# electron_v009.net
KiCad netlist of a schematic drawn in EAGLE
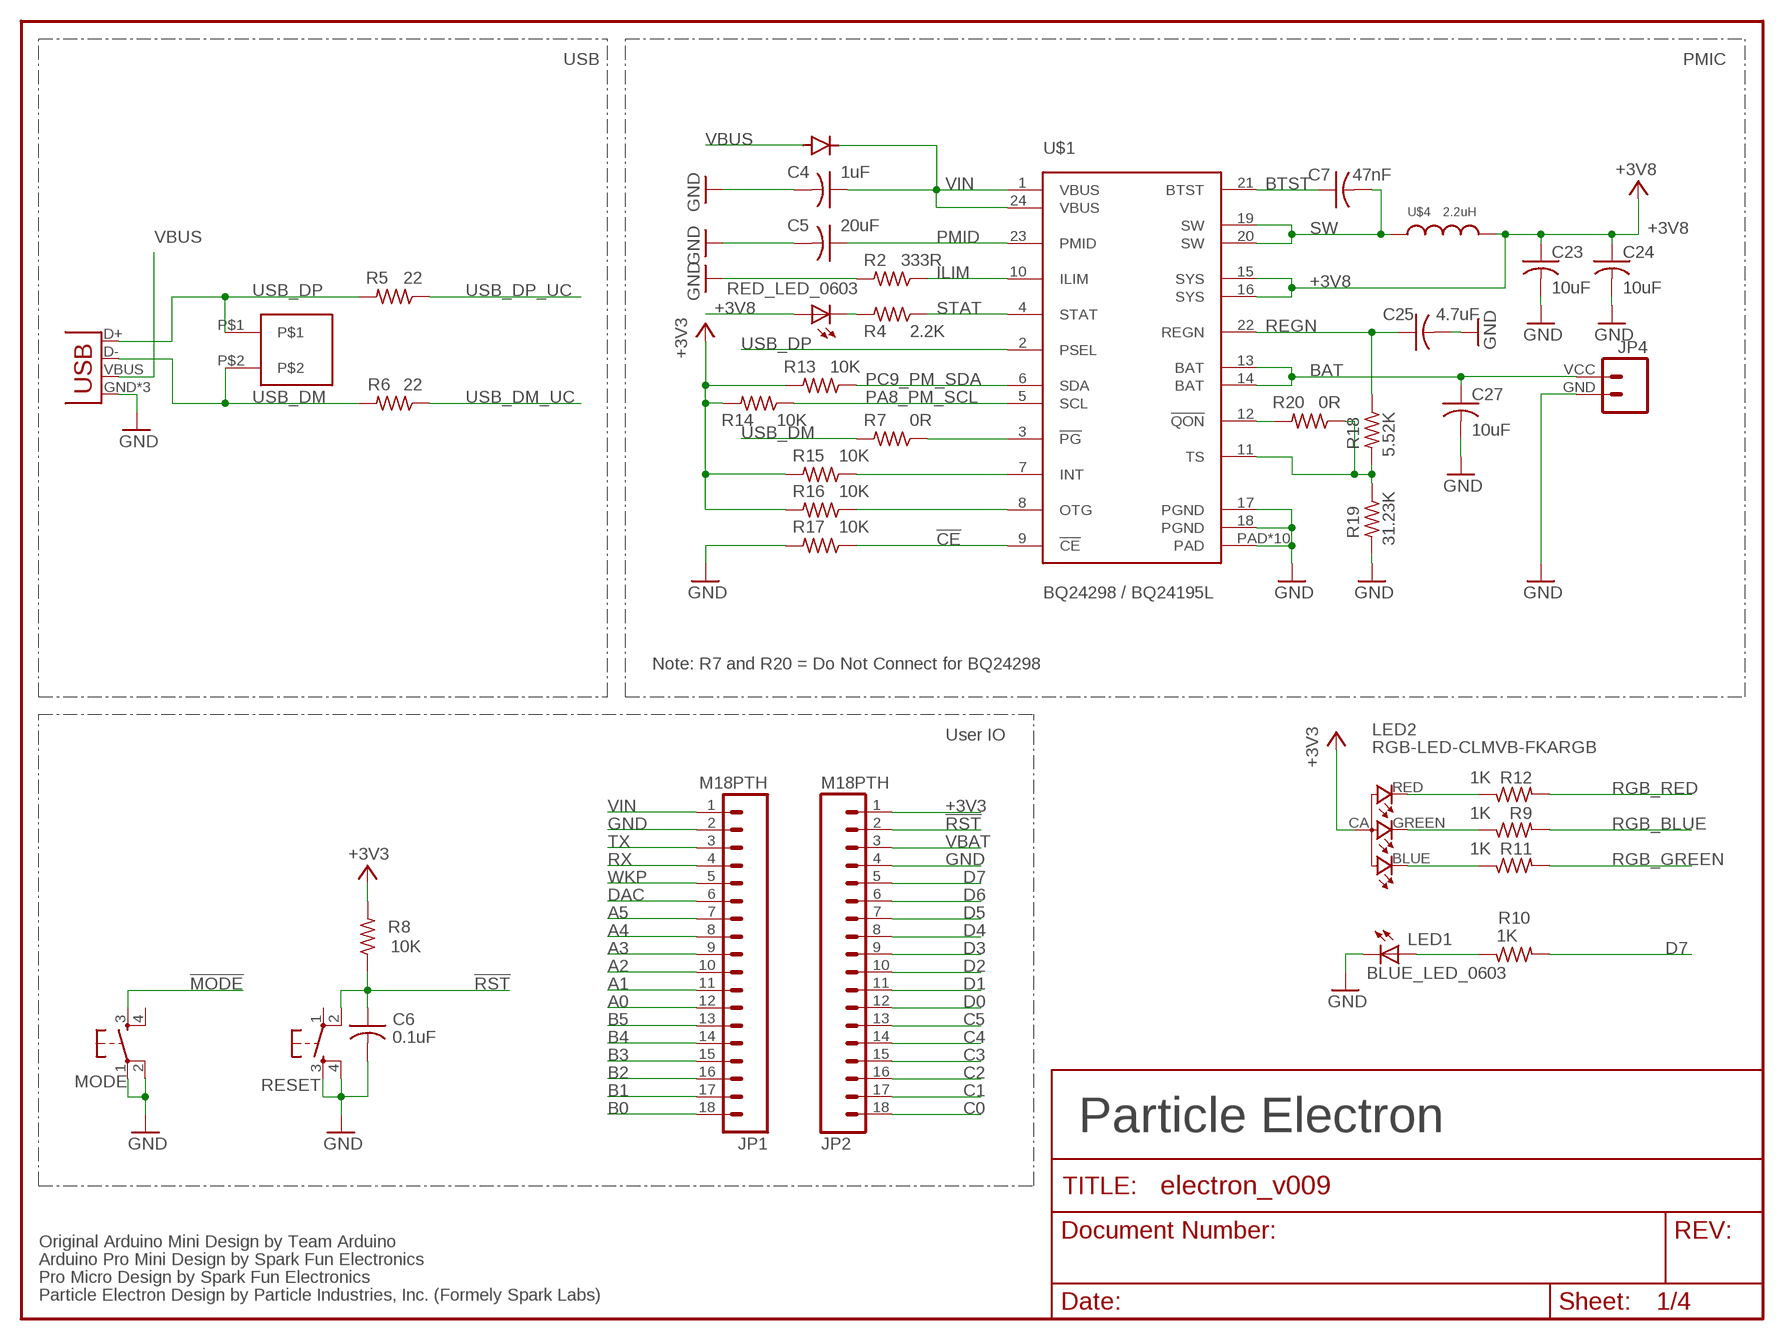
[diagram p0: schematic, sheet 1]
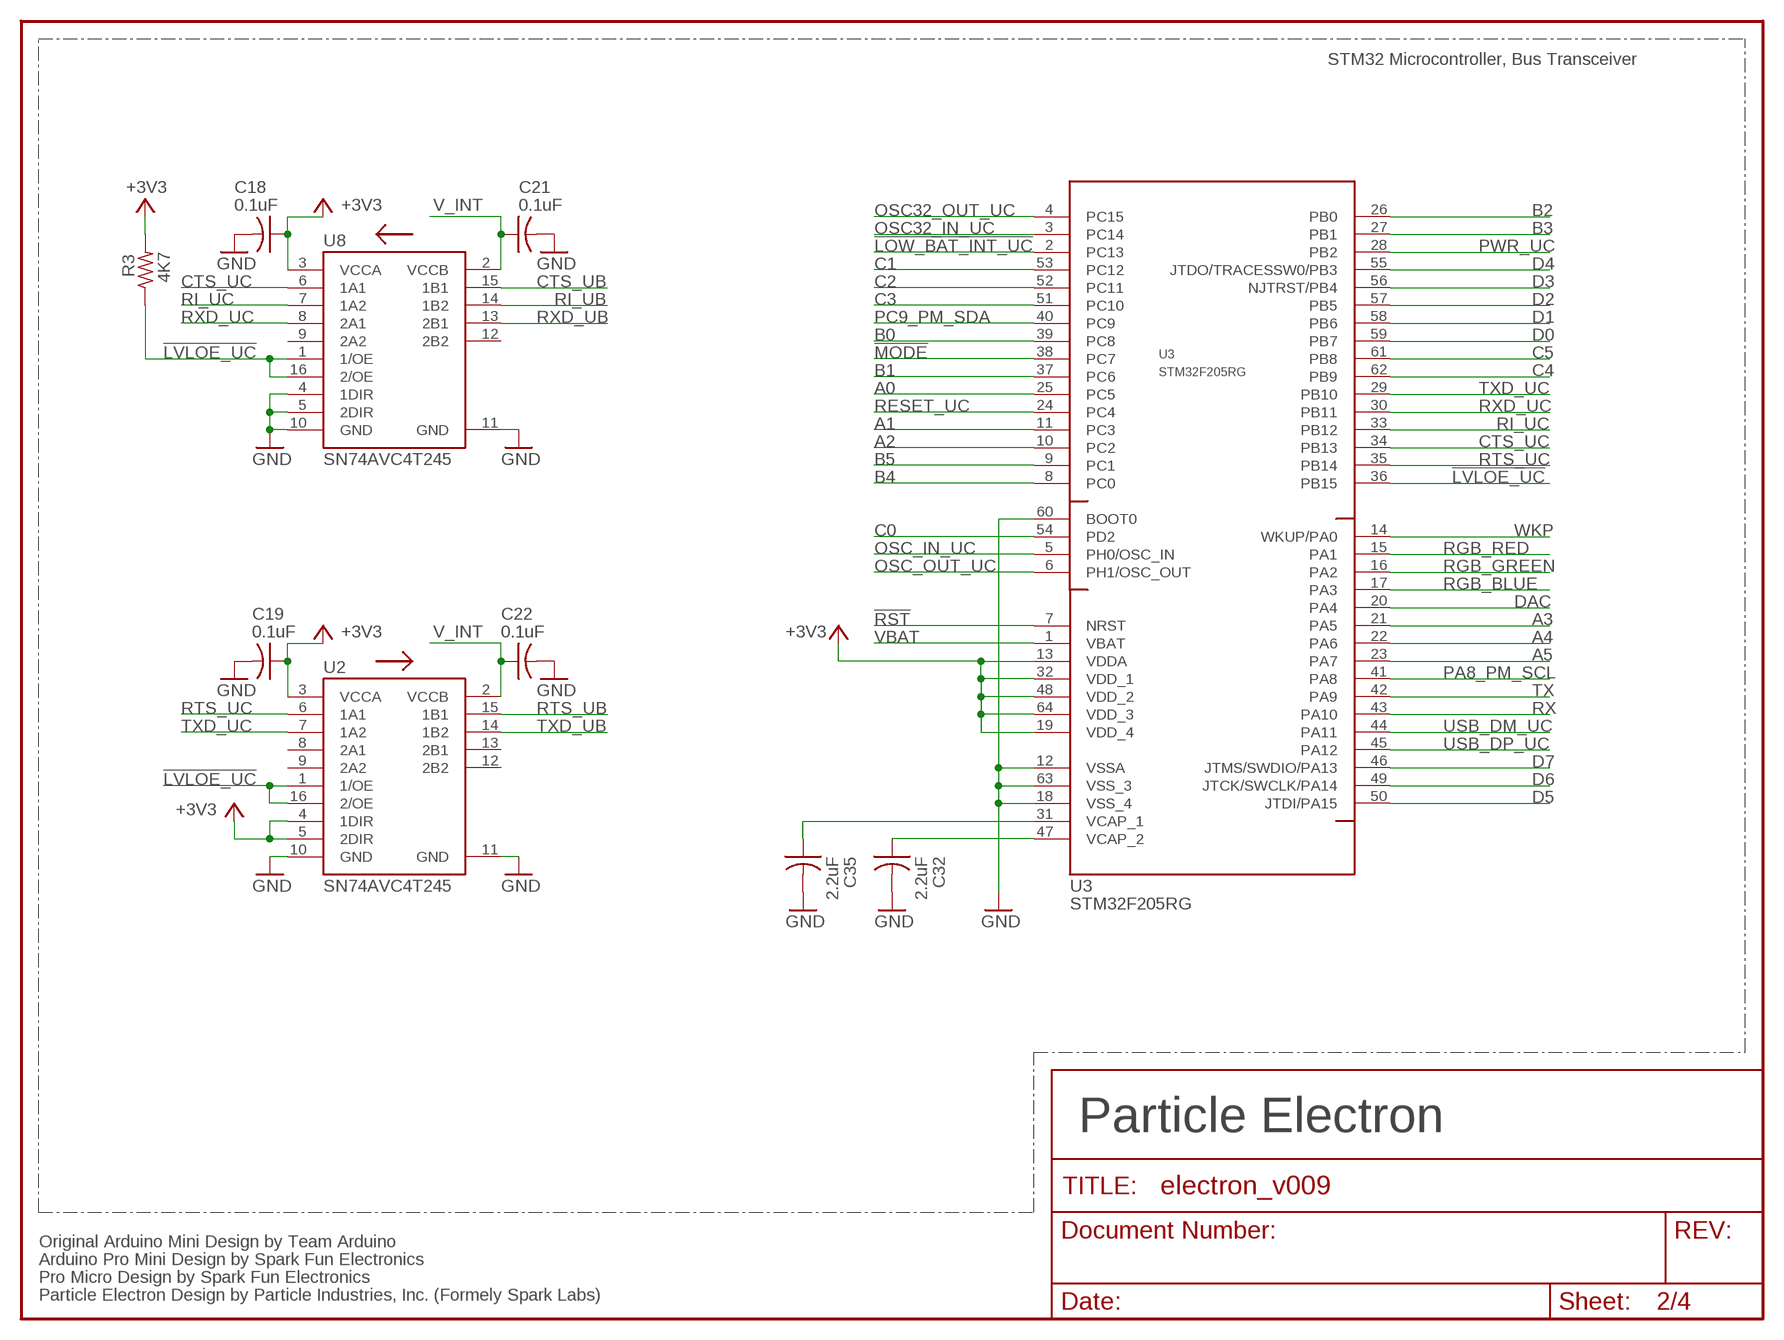
[diagram p1: schematic, sheet 2]
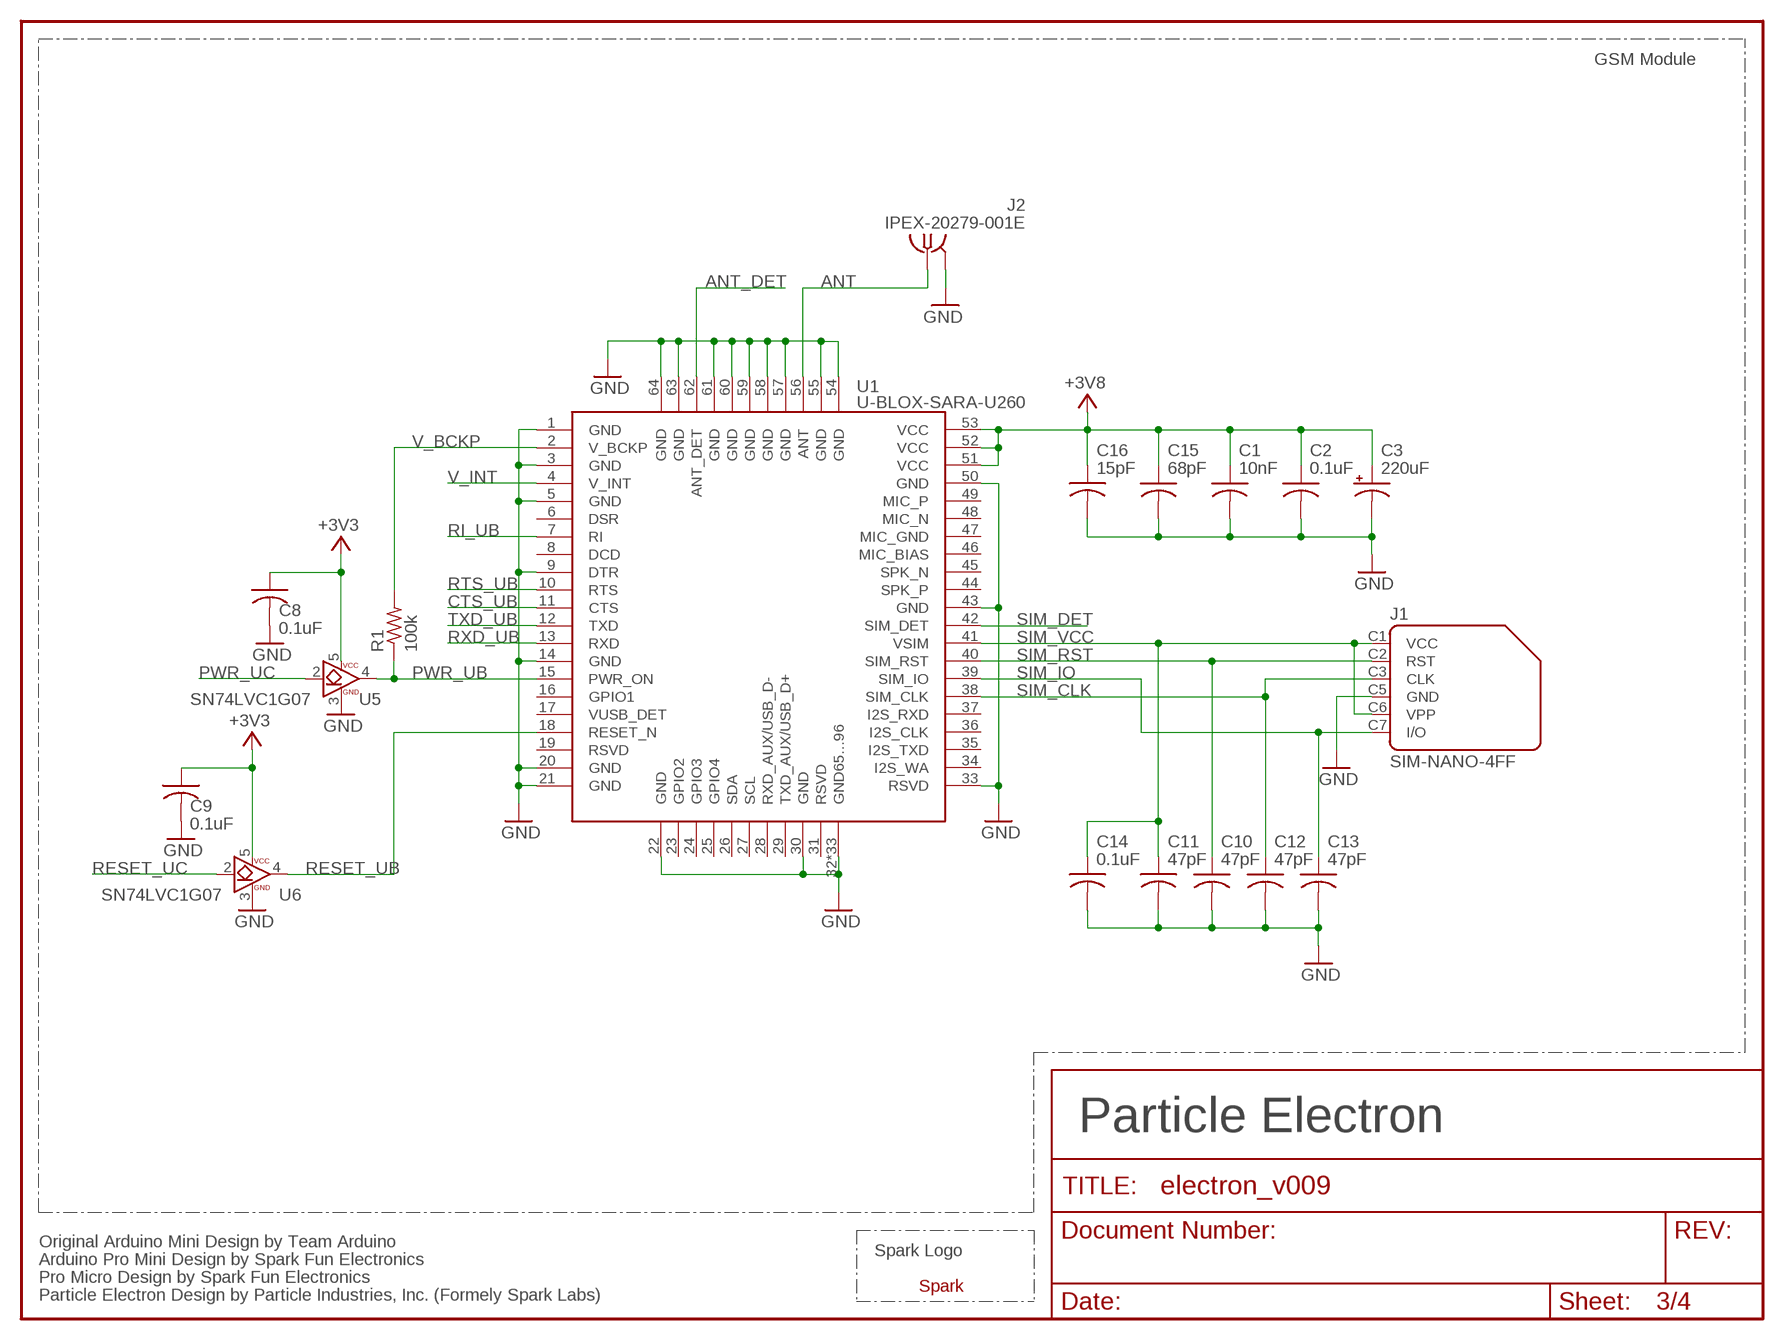
[diagram p2: schematic, sheet 3]
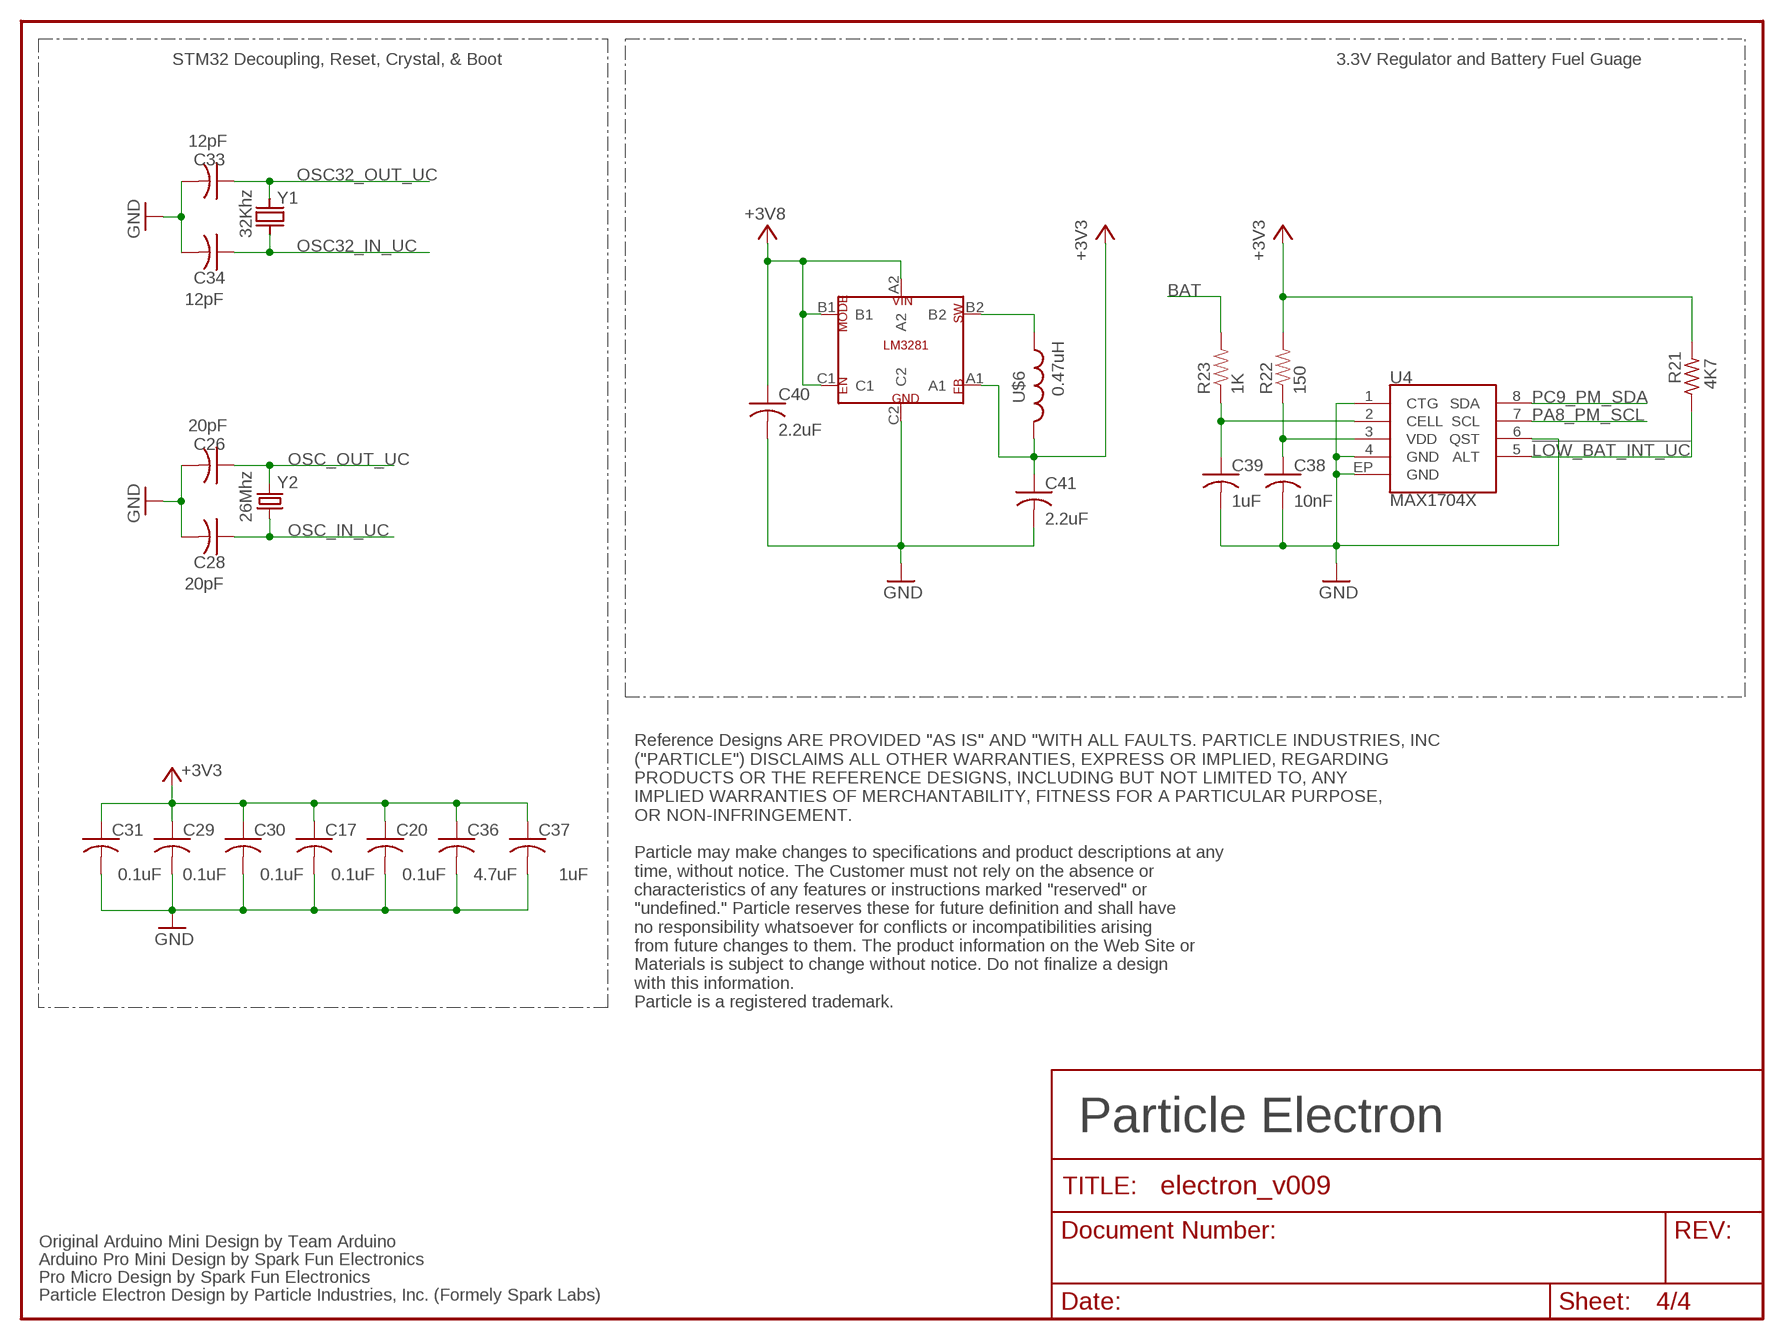
[diagram p3: schematic, sheet 4]

(export (version "E")
  (design (tool "Eeschema 10.0.6"))
  (components
    (comp (ref "C1")
      (value "10nF")
      (footprint "eagle-import:C0402_B")
      (libsource (lib "eagle-import") (part "C-US"))
    )
    (comp (ref "C2")
      (value "0.1uF")
      (footprint "eagle-import:C0402_B")
      (libsource (lib "eagle-import") (part "C-US"))
    )
    (comp (ref "C3")
      (value "220uF")
      (footprint "eagle-import:C_6032-28R")
      (libsource (lib "eagle-import") (part "CPOL-USC/6032-28R"))
    )
    (comp (ref "C8")
      (value "0.1uF")
      (footprint "eagle-import:C0402_B")
      (libsource (lib "eagle-import") (part "C-US"))
    )
    (comp (ref "C9")
      (value "0.1uF")
      (footprint "eagle-import:C0402_B")
      (libsource (lib "eagle-import") (part "C-US"))
    )
    (comp (ref "C10")
      (value "47pF")
      (footprint "eagle-import:C0402_B")
      (libsource (lib "eagle-import") (part "C-US"))
    )
    (comp (ref "C11")
      (value "47pF")
      (footprint "eagle-import:C0402_B")
      (libsource (lib "eagle-import") (part "C-US"))
    )
    (comp (ref "C12")
      (value "47pF")
      (footprint "eagle-import:C0402_B")
      (libsource (lib "eagle-import") (part "C-US"))
    )
    (comp (ref "C13")
      (value "47pF")
      (footprint "eagle-import:C0402_B")
      (libsource (lib "eagle-import") (part "C-US"))
    )
    (comp (ref "C14")
      (value "0.1uF")
      (footprint "eagle-import:C0402_B")
      (libsource (lib "eagle-import") (part "C-US"))
    )
    (comp (ref "C15")
      (value "68pF")
      (footprint "eagle-import:C0402_B")
      (libsource (lib "eagle-import") (part "C-US"))
    )
    (comp (ref "C16")
      (value "15pF")
      (footprint "eagle-import:C0402_B")
      (libsource (lib "eagle-import") (part "C-US"))
    )
    (comp (ref "J1")
      (value "SIM-NANO-4FF")
      (footprint "eagle-import:GCT-SIM8100")
      (libsource (lib "eagle-import") (part "SIM-NANO-4FF"))
    )
    (comp (ref "J2")
      (value "IPEX-20279-001E")
      (footprint "eagle-import:IPEX-20279-001E")
      (libsource (lib "eagle-import") (part "IPEX-20279-001E"))
    )
    (comp (ref "R1")
      (value "100k")
      (footprint "eagle-import:R0402_B")
      (libsource (lib "eagle-import") (part "R-US_"))
    )
    (comp (ref "U$2")
      (value "SPARK_LOGO2")
      (footprint "eagle-import:SPARK_LOGO2")
      (libsource (lib "eagle-import") (part "SPARK_LOGO2"))
    )
    (comp (ref "U1")
      (value "U-BLOX-SARA-U260")
      (footprint "eagle-import:U-BLOX-SARA-U2")
      (libsource (lib "eagle-import") (part "U-BLOX-SARA-U260"))
    )
    (comp (ref "U5")
      (value "SN74LVC1G07")
      (footprint "eagle-import:SC-70-5")
      (libsource (lib "eagle-import") (part "SN74LVC1G07"))
    )
    (comp (ref "U6")
      (value "SN74LVC1G07")
      (footprint "eagle-import:SC-70-5")
      (libsource (lib "eagle-import") (part "SN74LVC1G07"))
    )
    (comp (ref "C17")
      (value "0.1uF")
      (footprint "eagle-import:C0402_B")
      (libsource (lib "eagle-import") (part "C-US"))
    )
    (comp (ref "C20")
      (value "0.1uF")
      (footprint "eagle-import:C0402_B")
      (libsource (lib "eagle-import") (part "C-US"))
    )
    (comp (ref "C26")
      (value "20pF")
      (footprint "eagle-import:C0402_B")
      (libsource (lib "eagle-import") (part "C-US"))
    )
    (comp (ref "C28")
      (value "20pF")
      (footprint "eagle-import:C0402_B")
      (libsource (lib "eagle-import") (part "C-US"))
    )
    (comp (ref "C29")
      (value "0.1uF")
      (footprint "eagle-import:C0402_B")
      (libsource (lib "eagle-import") (part "C-US"))
    )
    (comp (ref "C30")
      (value "0.1uF")
      (footprint "eagle-import:C0402_B")
      (libsource (lib "eagle-import") (part "C-US"))
    )
    (comp (ref "C31")
      (value "0.1uF")
      (footprint "eagle-import:C0402_B")
      (libsource (lib "eagle-import") (part "C-US"))
    )
    (comp (ref "C33")
      (value "12pF")
      (footprint "eagle-import:C0402_B")
      (libsource (lib "eagle-import") (part "C-US"))
    )
    (comp (ref "C34")
      (value "12pF")
      (footprint "eagle-import:C0402_B")
      (libsource (lib "eagle-import") (part "C-US"))
    )
    (comp (ref "C36")
      (value "4.7uF")
      (footprint "eagle-import:C0402_B")
      (libsource (lib "eagle-import") (part "C-US"))
    )
    (comp (ref "C37")
      (value "1uF")
      (footprint "eagle-import:C0402_B")
      (libsource (lib "eagle-import") (part "C-US"))
    )
    (comp (ref "C38")
      (value "10nF")
      (footprint "eagle-import:C0402_B")
      (libsource (lib "eagle-import") (part "C-US"))
    )
    (comp (ref "C39")
      (value "1uF")
      (footprint "eagle-import:C0402_B")
      (libsource (lib "eagle-import") (part "C-US"))
    )
    (comp (ref "C40")
      (value "2.2uF")
      (footprint "eagle-import:C0603_B")
      (libsource (lib "eagle-import") (part "C-US0603"))
    )
    (comp (ref "C41")
      (value "2.2uF")
      (footprint "eagle-import:C0603_B")
      (libsource (lib "eagle-import") (part "C-US0603"))
    )
    (comp (ref "R21")
      (value "4K7")
      (footprint "eagle-import:R0402_B")
      (libsource (lib "eagle-import") (part "R-US_"))
    )
    (comp (ref "R22")
      (value "150")
      (footprint "eagle-import:0603-RES")
      (libsource (lib "eagle-import") (part "RESISTOR0603-RES"))
    )
    (comp (ref "R23")
      (value "1K")
      (footprint "eagle-import:0603-RES")
      (libsource (lib "eagle-import") (part "RESISTOR0603-RES"))
    )
    (comp (ref "U$5")
      (value "LM3281_DSBGA")
      (footprint "eagle-import:DSBGA")
      (libsource (lib "eagle-import") (part "LM3281_DSBGA"))
    )
    (comp (ref "U$6")
      (value "0.47uH")
      (footprint "eagle-import:0805")
      (libsource (lib "eagle-import") (part "INDUCTOR0805"))
    )
    (comp (ref "U4")
      (value "MAX1704X")
      (footprint "eagle-import:TDFN-8")
      (libsource (lib "eagle-import") (part "MAX1704X"))
    )
    (comp (ref "Y1")
      (value "32Khz")
      (footprint "eagle-import:FC135")
      (libsource (lib "eagle-import") (part "Q_FC135"))
    )
    (comp (ref "Y2")
      (value "26Mhz")
      (footprint "eagle-import:CRYSTAL-SMD-5X3")
      (libsource (lib "eagle-import") (part "CRYSTAL5X3"))
    )
    (comp (ref "C18")
      (value "0.1uF")
      (footprint "eagle-import:C0402_B")
      (libsource (lib "eagle-import") (part "C-US"))
    )
    (comp (ref "C19")
      (value "0.1uF")
      (footprint "eagle-import:C0402_B")
      (libsource (lib "eagle-import") (part "C-US"))
    )
    (comp (ref "C21")
      (value "0.1uF")
      (footprint "eagle-import:C0402_B")
      (libsource (lib "eagle-import") (part "C-US"))
    )
    (comp (ref "C22")
      (value "0.1uF")
      (footprint "eagle-import:C0402_B")
      (libsource (lib "eagle-import") (part "C-US"))
    )
    (comp (ref "C32")
      (value "2.2uF")
      (footprint "eagle-import:C0402_B")
      (libsource (lib "eagle-import") (part "C-US"))
    )
    (comp (ref "C35")
      (value "2.2uF")
      (footprint "eagle-import:C0402_B")
      (libsource (lib "eagle-import") (part "C-US"))
    )
    (comp (ref "R3")
      (value "4K7")
      (footprint "eagle-import:R0402_B")
      (libsource (lib "eagle-import") (part "R-US_"))
    )
    (comp (ref "U2")
      (value "SN74AVC4T245")
      (footprint "eagle-import:UFQFN-16")
      (libsource (lib "eagle-import") (part "SN74AVC4T245"))
    )
    (comp (ref "U3")
      (value "STM32F205RG")
      (footprint "eagle-import:LQFP64")
      (libsource (lib "eagle-import") (part "STM32F20XR"))
    )
    (comp (ref "U8")
      (value "SN74AVC4T245")
      (footprint "eagle-import:UFQFN-16")
      (libsource (lib "eagle-import") (part "SN74AVC4T245"))
    )
    (comp (ref "BLUE_LED_0603")
      (value "LED0603")
      (footprint "eagle-import:LED-0603")
      (libsource (lib "eagle-import") (part "LED0603"))
    )
    (comp (ref "C4")
      (value "1uF")
      (footprint "eagle-import:C0603_B")
      (libsource (lib "eagle-import") (part "C-US0603"))
    )
    (comp (ref "C5")
      (value "20uF")
      (footprint "eagle-import:C0603_B")
      (libsource (lib "eagle-import") (part "C-US0603"))
    )
    (comp (ref "C6")
      (value "0.1uF")
      (footprint "eagle-import:C0402_B")
      (libsource (lib "eagle-import") (part "C-US"))
    )
    (comp (ref "C7")
      (value "47nF")
      (footprint "eagle-import:C0402_B")
      (libsource (lib "eagle-import") (part "C-US"))
    )
    (comp (ref "C23")
      (value "10uF")
      (footprint "eagle-import:C0603_B")
      (libsource (lib "eagle-import") (part "C-US0603"))
    )
    (comp (ref "C24")
      (value "10uF")
      (footprint "eagle-import:C0603_B")
      (libsource (lib "eagle-import") (part "C-US0603"))
    )
    (comp (ref "C25")
      (value "4.7uF")
      (footprint "eagle-import:C0603_B")
      (libsource (lib "eagle-import") (part "C-US0603"))
    )
    (comp (ref "C27")
      (value "10uF")
      (footprint "eagle-import:C0603_B")
      (libsource (lib "eagle-import") (part "C-US0603"))
    )
    (comp (ref "JP1")
      (value "M18PTH")
      (footprint "eagle-import:1X18-SMALL-PADS")
      (libsource (lib "eagle-import") (part "M18PTH"))
    )
    (comp (ref "JP2")
      (value "M18PTH")
      (footprint "eagle-import:1X18-SMALL-PADS")
      (libsource (lib "eagle-import") (part "M18PTH"))
    )
    (comp (ref "JP4")
      (value "M024UCON-15767")
      (footprint "eagle-import:JST-2-SMD-VERT")
      (libsource (lib "eagle-import") (part "M024UCON-15767"))
    )
    (comp (ref "LED2")
      (value "RGB-LED-CLMVB-FKARGB")
      (footprint "eagle-import:PLCC4-2MM-RGB")
      (libsource (lib "eagle-import") (part "RGB-LED-CLMVB-FKARGB"))
    )
    (comp (ref "MODE")
      (value "KMR211GLFS")
      (footprint "eagle-import:TACTILE_SWITCH_SMD")
      (libsource (lib "eagle-import") (part "TAC_SWITCHSMD"))
    )
    (comp (ref "R2")
      (value "333R")
      (footprint "eagle-import:R0402_B")
      (libsource (lib "eagle-import") (part "R-US_"))
    )
    (comp (ref "R4")
      (value "2.2K")
      (footprint "eagle-import:R0402_B")
      (libsource (lib "eagle-import") (part "R-US_"))
    )
    (comp (ref "R5")
      (value "22")
      (footprint "eagle-import:R0402_B")
      (libsource (lib "eagle-import") (part "R-US_"))
    )
    (comp (ref "R6")
      (value "22")
      (footprint "eagle-import:R0402_B")
      (libsource (lib "eagle-import") (part "R-US_"))
    )
    (comp (ref "R7")
      (value "0R")
      (footprint "eagle-import:R0402_B")
      (libsource (lib "eagle-import") (part "R-US_"))
    )
    (comp (ref "R8")
      (value "10K")
      (footprint "eagle-import:R0402_B")
      (libsource (lib "eagle-import") (part "R-US_"))
    )
    (comp (ref "R9")
      (value "1K")
      (footprint "eagle-import:R0402_B")
      (libsource (lib "eagle-import") (part "R-US_"))
    )
    (comp (ref "R10")
      (value "1K")
      (footprint "eagle-import:R0402_B")
      (libsource (lib "eagle-import") (part "R-US_"))
    )
    (comp (ref "R11")
      (value "1K")
      (footprint "eagle-import:R0402_B")
      (libsource (lib "eagle-import") (part "R-US_"))
    )
    (comp (ref "R12")
      (value "1K")
      (footprint "eagle-import:R0402_B")
      (libsource (lib "eagle-import") (part "R-US_"))
    )
    (comp (ref "R13")
      (value "10K")
      (footprint "eagle-import:R0402_B")
      (libsource (lib "eagle-import") (part "R-US_"))
    )
    (comp (ref "R14")
      (value "10K")
      (footprint "eagle-import:R0402_B")
      (libsource (lib "eagle-import") (part "R-US_"))
    )
    (comp (ref "R15")
      (value "10K")
      (footprint "eagle-import:R0402_B")
      (libsource (lib "eagle-import") (part "R-US_"))
    )
    (comp (ref "R16")
      (value "10K")
      (footprint "eagle-import:R0402_B")
      (libsource (lib "eagle-import") (part "R-US_"))
    )
    (comp (ref "R17")
      (value "10K")
      (footprint "eagle-import:R0402_B")
      (libsource (lib "eagle-import") (part "R-US_"))
    )
    (comp (ref "R18")
      (value "5.52K")
      (footprint "eagle-import:R0402_B")
      (libsource (lib "eagle-import") (part "R-US_"))
    )
    (comp (ref "R19")
      (value "31.23K")
      (footprint "eagle-import:R0402_B")
      (libsource (lib "eagle-import") (part "R-US_"))
    )
    (comp (ref "R20")
      (value "0R")
      (footprint "eagle-import:R0402_B")
      (libsource (lib "eagle-import") (part "R-US_"))
    )
    (comp (ref "RED_LED_0603")
      (value "LED0603")
      (footprint "eagle-import:LED-0603")
      (libsource (lib "eagle-import") (part "LED0603"))
    )
    (comp (ref "RESET")
      (value "KMR211GLFS")
      (footprint "eagle-import:TACTILE_SWITCH_SMD")
      (libsource (lib "eagle-import") (part "TAC_SWITCHSMD"))
    )
    (comp (ref "U$1")
      (value "BQ24298 / BQ24195L")
      (footprint "eagle-import:QFN24")
      (libsource (lib "eagle-import") (part "BQ24298RTWR"))
    )
    (comp (ref "U$3")
      (value "DIODE")
      (footprint "eagle-import:DIODE-DO-220AA(SMP)")
      (libsource (lib "eagle-import") (part "DIODE"))
    )
    (comp (ref "U$4")
      (value "2.2uH")
      (footprint "eagle-import:4020TYPE")
      (libsource (lib "eagle-import") (part "INDUCTOR4020"))
    )
    (comp (ref "U$7")
      (value "M02_0.05_HEADER")
      (footprint "eagle-import:M02_0.05_HEADER")
      (libsource (lib "eagle-import") (part "M02_0.05_HEADER"))
    )
    (comp (ref "X1")
      (value "USB-MICROB")
      (footprint "eagle-import:USB-MICROB-SLOT-HOLE")
      (libsource (lib "eagle-import") (part "USBUSB-MICROB-SLOT-HOLE"))
    )
  )
  (nets
    (net (code "1") (name "+3V3") (class "Default")
      (node (ref "C17") (pin "1") (pinfunction "1_1") (pintype "passive"))
      (node (ref "C18") (pin "1") (pinfunction "1_1") (pintype "passive"))
      (node (ref "C19") (pin "1") (pinfunction "1_1") (pintype "passive"))
      (node (ref "C20") (pin "1") (pinfunction "1_1") (pintype "passive"))
      (node (ref "C29") (pin "1") (pinfunction "1_1") (pintype "passive"))
      (node (ref "C30") (pin "1") (pinfunction "1_1") (pintype "passive"))
      (node (ref "C31") (pin "1") (pinfunction "1_1") (pintype "passive"))
      (node (ref "C36") (pin "1") (pinfunction "1_1") (pintype "passive"))
      (node (ref "C37") (pin "1") (pinfunction "1_1") (pintype "passive"))
      (node (ref "C41") (pin "1") (pinfunction "1_1") (pintype "passive"))
      (node (ref "C8") (pin "1") (pinfunction "1_1") (pintype "passive"))
      (node (ref "C9") (pin "1") (pinfunction "1_1") (pintype "passive"))
      (node (ref "JP2") (pin "1") (pinfunction "1_1") (pintype "passive"))
      (node (ref "LED2") (pin "CA") (pinfunction "1_CA") (pintype "passive"))
      (node (ref "R13") (pin "2") (pinfunction "2_2") (pintype "passive"))
      (node (ref "R14") (pin "2") (pinfunction "2_2") (pintype "passive"))
      (node (ref "R15") (pin "2") (pinfunction "2_2") (pintype "passive"))
      (node (ref "R16") (pin "2") (pinfunction "2_2") (pintype "passive"))
      (node (ref "R21") (pin "2") (pinfunction "2_2") (pintype "passive"))
      (node (ref "R22") (pin "2") (pinfunction "2_2") (pintype "passive"))
      (node (ref "R3") (pin "2") (pinfunction "2_2") (pintype "passive"))
      (node (ref "R8") (pin "2") (pinfunction "2_2") (pintype "passive"))
      (node (ref "U$5") (pin "A1") (pinfunction "A1_A1") (pintype "bidirectional"))
      (node (ref "U$6") (pin "2") (pinfunction "2_2") (pintype "passive"))
      (node (ref "U2") (pin "3") (pinfunction "VCCA_3") (pintype "bidirectional"))
      (node (ref "U2") (pin "4") (pinfunction "1DIR_4") (pintype "bidirectional"))
      (node (ref "U2") (pin "5") (pinfunction "2DIR_5") (pintype "bidirectional"))
      (node (ref "U3") (pin "13") (pinfunction "VDDA_13") (pintype "power_in"))
      (node (ref "U3") (pin "19") (pinfunction "VDD_4_19") (pintype "power_in"))
      (node (ref "U3") (pin "32") (pinfunction "VDD_1_32") (pintype "power_in"))
      (node (ref "U3") (pin "48") (pinfunction "VDD_2_48") (pintype "power_in"))
      (node (ref "U3") (pin "64") (pinfunction "VDD_3_64") (pintype "power_in"))
      (node (ref "U5") (pin "5") (pinfunction "VCC_5") (pintype "bidirectional"))
      (node (ref "U6") (pin "5") (pinfunction "VCC_5") (pintype "bidirectional"))
      (node (ref "U8") (pin "3") (pinfunction "VCCA_3") (pintype "bidirectional"))
    )
    (net (code "2") (name "+3V8") (class "Default")
      (node (ref "C1") (pin "1") (pinfunction "1_1") (pintype "passive"))
      (node (ref "C15") (pin "1") (pinfunction "1_1") (pintype "passive"))
      (node (ref "C16") (pin "1") (pinfunction "1_1") (pintype "passive"))
      (node (ref "C2") (pin "1") (pinfunction "1_1") (pintype "passive"))
      (node (ref "C23") (pin "1") (pinfunction "1_1") (pintype "passive"))
      (node (ref "C24") (pin "1") (pinfunction "1_1") (pintype "passive"))
      (node (ref "C3") (pin "+") (pinfunction "+_+") (pintype "passive"))
      (node (ref "C40") (pin "1") (pinfunction "1_1") (pintype "passive"))
      (node (ref "RED_LED_0603") (pin "A") (pinfunction "A_A") (pintype "passive"))
      (node (ref "U$1") (pin "15") (pinfunction "SYS_15") (pintype "power_in"))
      (node (ref "U$1") (pin "16") (pinfunction "SYS_16") (pintype "power_in"))
      (node (ref "U$4") (pin "P$2") (pinfunction "2_P$2") (pintype "bidirectional"))
      (node (ref "U$5") (pin "A2") (pinfunction "A2_A2") (pintype "bidirectional"))
      (node (ref "U$5") (pin "B1") (pinfunction "B1_B1") (pintype "bidirectional"))
      (node (ref "U$5") (pin "C1") (pinfunction "C1_C1") (pintype "bidirectional"))
      (node (ref "U1") (pin "51") (pinfunction "VCC_51") (pintype "bidirectional"))
      (node (ref "U1") (pin "52") (pinfunction "VCC_52") (pintype "bidirectional"))
      (node (ref "U1") (pin "53") (pinfunction "VCC_53") (pintype "bidirectional"))
    )
    (net (code "3") (name "A0") (class "Default")
      (node (ref "JP1") (pin "12") (pinfunction "12_12") (pintype "passive"))
      (node (ref "U3") (pin "25") (pinfunction "PC5_25") (pintype "bidirectional"))
    )
    (net (code "4") (name "A1") (class "Default")
      (node (ref "JP1") (pin "11") (pinfunction "11_11") (pintype "passive"))
      (node (ref "U3") (pin "11") (pinfunction "PC3_11") (pintype "bidirectional"))
    )
    (net (code "5") (name "A2") (class "Default")
      (node (ref "JP1") (pin "10") (pinfunction "10_10") (pintype "passive"))
      (node (ref "U3") (pin "10") (pinfunction "PC2_10") (pintype "bidirectional"))
    )
    (net (code "6") (name "A3") (class "Default")
      (node (ref "JP1") (pin "9") (pinfunction "9_9") (pintype "passive"))
      (node (ref "U3") (pin "21") (pinfunction "PA5_21") (pintype "bidirectional"))
    )
    (net (code "7") (name "A4") (class "Default")
      (node (ref "JP1") (pin "8") (pinfunction "8_8") (pintype "passive"))
      (node (ref "U3") (pin "22") (pinfunction "PA6_22") (pintype "bidirectional"))
    )
    (net (code "8") (name "A5") (class "Default")
      (node (ref "JP1") (pin "7") (pinfunction "7_7") (pintype "passive"))
      (node (ref "U3") (pin "23") (pinfunction "PA7_23") (pintype "bidirectional"))
    )
    (net (code "9") (name "ANT") (class "Default")
      (node (ref "J2") (pin "1") (pinfunction "1_1") (pintype "passive"))
      (node (ref "U1") (pin "56") (pinfunction "ANT_56") (pintype "bidirectional"))
    )
    (net (code "10") (name "ANT_DET") (class "Default")
      (node (ref "U1") (pin "62") (pinfunction "ANT_DET_62") (pintype "bidirectional"))
    )
    (net (code "11") (name "B0") (class "Default")
      (node (ref "JP1") (pin "18") (pinfunction "18_18") (pintype "passive"))
      (node (ref "U3") (pin "39") (pinfunction "PC8_39") (pintype "bidirectional"))
    )
    (net (code "12") (name "B1") (class "Default")
      (node (ref "JP1") (pin "17") (pinfunction "17_17") (pintype "passive"))
      (node (ref "U3") (pin "37") (pinfunction "PC6_37") (pintype "bidirectional"))
    )
    (net (code "13") (name "B2") (class "Default")
      (node (ref "JP1") (pin "16") (pinfunction "16_16") (pintype "passive"))
      (node (ref "U3") (pin "26") (pinfunction "PB0_26") (pintype "bidirectional"))
    )
    (net (code "14") (name "B3") (class "Default")
      (node (ref "JP1") (pin "15") (pinfunction "15_15") (pintype "passive"))
      (node (ref "U3") (pin "27") (pinfunction "PB1_27") (pintype "bidirectional"))
    )
    (net (code "15") (name "B4") (class "Default")
      (node (ref "JP1") (pin "14") (pinfunction "14_14") (pintype "passive"))
      (node (ref "U3") (pin "8") (pinfunction "PC0_8") (pintype "bidirectional"))
    )
    (net (code "16") (name "B5") (class "Default")
      (node (ref "JP1") (pin "13") (pinfunction "13_13") (pintype "passive"))
      (node (ref "U3") (pin "9") (pinfunction "PC1_9") (pintype "bidirectional"))
    )
    (net (code "17") (name "BAT") (class "Default")
      (node (ref "C27") (pin "1") (pinfunction "1_1") (pintype "passive"))
      (node (ref "JP4") (pin "VCC") (pinfunction "2_VCC") (pintype "passive"))
      (node (ref "R23") (pin "2") (pinfunction "2_2") (pintype "passive"))
      (node (ref "U$1") (pin "13") (pinfunction "BAT_13") (pintype "passive"))
      (node (ref "U$1") (pin "14") (pinfunction "BAT_14") (pintype "power_in"))
    )
    (net (code "18") (name "BTST") (class "Default")
      (node (ref "C7") (pin "1") (pinfunction "1_1") (pintype "passive"))
      (node (ref "U$1") (pin "21") (pinfunction "BTST_21") (pintype "bidirectional"))
    )
    (net (code "19") (name "C0") (class "Default")
      (node (ref "JP2") (pin "18") (pinfunction "18_18") (pintype "passive"))
      (node (ref "U3") (pin "54") (pinfunction "PD2_54") (pintype "bidirectional"))
    )
    (net (code "20") (name "C1") (class "Default")
      (node (ref "JP2") (pin "17") (pinfunction "17_17") (pintype "passive"))
      (node (ref "U3") (pin "53") (pinfunction "PC12_53") (pintype "bidirectional"))
    )
    (net (code "21") (name "C2") (class "Default")
      (node (ref "JP2") (pin "16") (pinfunction "16_16") (pintype "passive"))
      (node (ref "U3") (pin "52") (pinfunction "PC11_52") (pintype "bidirectional"))
    )
    (net (code "22") (name "C3") (class "Default")
      (node (ref "JP2") (pin "15") (pinfunction "15_15") (pintype "passive"))
      (node (ref "U3") (pin "51") (pinfunction "PC10_51") (pintype "bidirectional"))
    )
    (net (code "23") (name "C4") (class "Default")
      (node (ref "JP2") (pin "14") (pinfunction "14_14") (pintype "passive"))
      (node (ref "U3") (pin "62") (pinfunction "PB9_62") (pintype "bidirectional"))
    )
    (net (code "24") (name "C5") (class "Default")
      (node (ref "JP2") (pin "13") (pinfunction "13_13") (pintype "passive"))
      (node (ref "U3") (pin "61") (pinfunction "PB8_61") (pintype "bidirectional"))
    )
    (net (code "25") (name "CTS_UB") (class "Default")
      (node (ref "U1") (pin "11") (pinfunction "CTS_11") (pintype "bidirectional"))
      (node (ref "U8") (pin "15") (pinfunction "1B1_15") (pintype "bidirectional"))
    )
    (net (code "26") (name "CTS_UC") (class "Default")
      (node (ref "U3") (pin "34") (pinfunction "PB13_34") (pintype "bidirectional"))
      (node (ref "U8") (pin "6") (pinfunction "1A1_6") (pintype "bidirectional"))
    )
    (net (code "27") (name "D0") (class "Default")
      (node (ref "JP2") (pin "12") (pinfunction "12_12") (pintype "passive"))
      (node (ref "U3") (pin "59") (pinfunction "PB7_59") (pintype "bidirectional"))
    )
    (net (code "28") (name "D1") (class "Default")
      (node (ref "JP2") (pin "11") (pinfunction "11_11") (pintype "passive"))
      (node (ref "U3") (pin "58") (pinfunction "PB6_58") (pintype "bidirectional"))
    )
    (net (code "29") (name "D2") (class "Default")
      (node (ref "JP2") (pin "10") (pinfunction "10_10") (pintype "passive"))
      (node (ref "U3") (pin "57") (pinfunction "PB5_57") (pintype "bidirectional"))
    )
    (net (code "30") (name "D3") (class "Default")
      (node (ref "JP2") (pin "9") (pinfunction "9_9") (pintype "passive"))
      (node (ref "U3") (pin "56") (pinfunction "NJTRST/PB4_56") (pintype "bidirectional"))
    )
    (net (code "31") (name "D4") (class "Default")
      (node (ref "JP2") (pin "8") (pinfunction "8_8") (pintype "passive"))
      (node (ref "U3") (pin "55") (pinfunction "JTDO/TRACESSW0/PB3_55") (pintype "bidirectional"))
    )
    (net (code "32") (name "D5") (class "Default")
      (node (ref "JP2") (pin "7") (pinfunction "7_7") (pintype "passive"))
      (node (ref "U3") (pin "50") (pinfunction "JTDI/PA15_50") (pintype "bidirectional"))
    )
    (net (code "33") (name "D6") (class "Default")
      (node (ref "JP2") (pin "6") (pinfunction "6_6") (pintype "passive"))
      (node (ref "U3") (pin "49") (pinfunction "JTCK/SWCLK/PA14_49") (pintype "bidirectional"))
    )
    (net (code "34") (name "D7") (class "Default")
      (node (ref "JP2") (pin "5") (pinfunction "5_5") (pintype "passive"))
      (node (ref "R10") (pin "2") (pinfunction "2_2") (pintype "passive"))
      (node (ref "U3") (pin "46") (pinfunction "JTMS/SWDIO/PA13_46") (pintype "bidirectional"))
    )
    (net (code "35") (name "DAC") (class "Default")
      (node (ref "JP1") (pin "6") (pinfunction "6_6") (pintype "passive"))
      (node (ref "U3") (pin "20") (pinfunction "PA4_20") (pintype "bidirectional"))
    )
    (net (code "36") (name "GND") (class "Default")
      (node (ref "BLUE_LED_0603") (pin "C") (pinfunction "C_C") (pintype "passive"))
      (node (ref "C1") (pin "2") (pinfunction "2_2") (pintype "passive"))
      (node (ref "C10") (pin "2") (pinfunction "2_2") (pintype "passive"))
      (node (ref "C11") (pin "2") (pinfunction "2_2") (pintype "passive"))
      (node (ref "C12") (pin "2") (pinfunction "2_2") (pintype "passive"))
      (node (ref "C13") (pin "2") (pinfunction "2_2") (pintype "passive"))
      (node (ref "C14") (pin "2") (pinfunction "2_2") (pintype "passive"))
      (node (ref "C15") (pin "2") (pinfunction "2_2") (pintype "passive"))
      (node (ref "C16") (pin "2") (pinfunction "2_2") (pintype "passive"))
      (node (ref "C17") (pin "2") (pinfunction "2_2") (pintype "passive"))
      (node (ref "C18") (pin "2") (pinfunction "2_2") (pintype "passive"))
      (node (ref "C19") (pin "2") (pinfunction "2_2") (pintype "passive"))
      (node (ref "C2") (pin "2") (pinfunction "2_2") (pintype "passive"))
      (node (ref "C20") (pin "2") (pinfunction "2_2") (pintype "passive"))
      (node (ref "C21") (pin "2") (pinfunction "2_2") (pintype "passive"))
      (node (ref "C22") (pin "2") (pinfunction "2_2") (pintype "passive"))
      (node (ref "C23") (pin "2") (pinfunction "2_2") (pintype "passive"))
      (node (ref "C24") (pin "2") (pinfunction "2_2") (pintype "passive"))
      (node (ref "C25") (pin "2") (pinfunction "2_2") (pintype "passive"))
      (node (ref "C26") (pin "2") (pinfunction "2_2") (pintype "passive"))
      (node (ref "C27") (pin "2") (pinfunction "2_2") (pintype "passive"))
      (node (ref "C28") (pin "2") (pinfunction "2_2") (pintype "passive"))
      (node (ref "C29") (pin "2") (pinfunction "2_2") (pintype "passive"))
      (node (ref "C3") (pin "-") (pinfunction "-_-") (pintype "passive"))
      (node (ref "C30") (pin "2") (pinfunction "2_2") (pintype "passive"))
      (node (ref "C31") (pin "2") (pinfunction "2_2") (pintype "passive"))
      (node (ref "C32") (pin "2") (pinfunction "2_2") (pintype "passive"))
      (node (ref "C33") (pin "2") (pinfunction "2_2") (pintype "passive"))
      (node (ref "C34") (pin "2") (pinfunction "2_2") (pintype "passive"))
      (node (ref "C35") (pin "2") (pinfunction "2_2") (pintype "passive"))
      (node (ref "C36") (pin "2") (pinfunction "2_2") (pintype "passive"))
      (node (ref "C37") (pin "2") (pinfunction "2_2") (pintype "passive"))
      (node (ref "C38") (pin "2") (pinfunction "2_2") (pintype "passive"))
      (node (ref "C39") (pin "2") (pinfunction "2_2") (pintype "passive"))
      (node (ref "C4") (pin "2") (pinfunction "2_2") (pintype "passive"))
      (node (ref "C40") (pin "2") (pinfunction "2_2") (pintype "passive"))
      (node (ref "C41") (pin "2") (pinfunction "2_2") (pintype "passive"))
      (node (ref "C5") (pin "2") (pinfunction "2_2") (pintype "passive"))
      (node (ref "C6") (pin "2") (pinfunction "2_2") (pintype "passive"))
      (node (ref "C8") (pin "2") (pinfunction "2_2") (pintype "passive"))
      (node (ref "C9") (pin "2") (pinfunction "2_2") (pintype "passive"))
      (node (ref "J1") (pin "C5") (pinfunction "GND_C5") (pintype "passive"))
      (node (ref "J2") (pin "2@1") (pinfunction "GND_2@1") (pintype "passive"))
      (node (ref "J2") (pin "2@2") (pinfunction "GND_2@2") (pintype "passive"))
      (node (ref "JP1") (pin "2") (pinfunction "2_2") (pintype "passive"))
      (node (ref "JP2") (pin "4") (pinfunction "4_4") (pintype "passive"))
      (node (ref "JP4") (pin "GND") (pinfunction "1_GND") (pintype "passive"))
      (node (ref "MODE") (pin "1") (pinfunction "1_1") (pintype "passive"))
      (node (ref "MODE") (pin "2") (pinfunction "2_2") (pintype "passive"))
      (node (ref "R17") (pin "2") (pinfunction "2_2") (pintype "passive"))
      (node (ref "R19") (pin "2") (pinfunction "2_2") (pintype "passive"))
      (node (ref "R2") (pin "2") (pinfunction "2_2") (pintype "passive"))
      (node (ref "RESET") (pin "3") (pinfunction "3_3") (pintype "passive"))
      (node (ref "RESET") (pin "4") (pinfunction "4_4") (pintype "passive"))
      (node (ref "U$1") (pin "17") (pinfunction "PGND_17") (pintype "passive"))
      (node (ref "U$1") (pin "18") (pinfunction "PGND_18") (pintype "passive"))
      (node (ref "U$1") (pin "PAD") (pinfunction "PAD_PAD") (pintype "power_in"))
      (node (ref "U$1") (pin "PAD@1") (pinfunction "PAD_PAD@1") (pintype "power_in"))
      (node (ref "U$1") (pin "PAD@2") (pinfunction "PAD_PAD@2") (pintype "power_in"))
      (node (ref "U$1") (pin "PAD@3") (pinfunction "PAD_PAD@3") (pintype "power_in"))
      (node (ref "U$1") (pin "PAD@4") (pinfunction "PAD_PAD@4") (pintype "power_in"))
      (node (ref "U$1") (pin "PAD@5") (pinfunction "PAD_PAD@5") (pintype "power_in"))
      (node (ref "U$1") (pin "PAD@6") (pinfunction "PAD_PAD@6") (pintype "power_in"))
      (node (ref "U$1") (pin "PAD@7") (pinfunction "PAD_PAD@7") (pintype "power_in"))
      (node (ref "U$1") (pin "PAD@8") (pinfunction "PAD_PAD@8") (pintype "power_in"))
      (node (ref "U$1") (pin "PAD@9") (pinfunction "PAD_PAD@9") (pintype "power_in"))
      (node (ref "U$5") (pin "C2") (pinfunction "C2_C2") (pintype "bidirectional"))
      (node (ref "U1") (pin "1") (pinfunction "GND_1") (pintype "bidirectional"))
      (node (ref "U1") (pin "14") (pinfunction "GND_14") (pintype "bidirectional"))
      (node (ref "U1") (pin "20") (pinfunction "GND_20") (pintype "bidirectional"))
      (node (ref "U1") (pin "21") (pinfunction "GND_21") (pintype "bidirectional"))
      (node (ref "U1") (pin "22") (pinfunction "GND_22") (pintype "bidirectional"))
      (node (ref "U1") (pin "3") (pinfunction "GND_3") (pintype "bidirectional"))
      (node (ref "U1") (pin "30") (pinfunction "GND_30") (pintype "bidirectional"))
      (node (ref "U1") (pin "32") (pinfunction "GND65...96_32") (pintype "bidirectional"))
      (node (ref "U1") (pin "33") (pinfunction "RSVD_33") (pintype "bidirectional"))
      (node (ref "U1") (pin "43") (pinfunction "GND_43") (pintype "bidirectional"))
      (node (ref "U1") (pin "5") (pinfunction "GND_5") (pintype "bidirectional"))
      (node (ref "U1") (pin "50") (pinfunction "GND_50") (pintype "bidirectional"))
      (node (ref "U1") (pin "54") (pinfunction "GND_54") (pintype "bidirectional"))
      (node (ref "U1") (pin "55") (pinfunction "GND_55") (pintype "bidirectional"))
      (node (ref "U1") (pin "57") (pinfunction "GND_57") (pintype "bidirectional"))
      (node (ref "U1") (pin "58") (pinfunction "GND_58") (pintype "bidirectional"))
      (node (ref "U1") (pin "59") (pinfunction "GND_59") (pintype "bidirectional"))
      (node (ref "U1") (pin "60") (pinfunction "GND_60") (pintype "bidirectional"))
      (node (ref "U1") (pin "61") (pinfunction "GND_61") (pintype "bidirectional"))
      (node (ref "U1") (pin "63") (pinfunction "GND_63") (pintype "bidirectional"))
      (node (ref "U1") (pin "64") (pinfunction "GND_64") (pintype "bidirectional"))
      (node (ref "U1") (pin "65") (pinfunction "GND65...96_65") (pintype "bidirectional"))
      (node (ref "U1") (pin "66") (pinfunction "GND65...96_66") (pintype "bidirectional"))
      (node (ref "U1") (pin "67") (pinfunction "GND65...96_67") (pintype "bidirectional"))
      (node (ref "U1") (pin "68") (pinfunction "GND65...96_68") (pintype "bidirectional"))
      (node (ref "U1") (pin "69") (pinfunction "GND65...96_69") (pintype "bidirectional"))
      (node (ref "U1") (pin "70") (pinfunction "GND65...96_70") (pintype "bidirectional"))
      (node (ref "U1") (pin "71") (pinfunction "GND65...96_71") (pintype "bidirectional"))
      (node (ref "U1") (pin "72") (pinfunction "GND65...96_72") (pintype "bidirectional"))
      (node (ref "U1") (pin "73") (pinfunction "GND65...96_73") (pintype "bidirectional"))
      (node (ref "U1") (pin "74") (pinfunction "GND65...96_74") (pintype "bidirectional"))
      (node (ref "U1") (pin "75") (pinfunction "GND65...96_75") (pintype "bidirectional"))
      (node (ref "U1") (pin "76") (pinfunction "GND65...96_76") (pintype "bidirectional"))
      (node (ref "U1") (pin "77") (pinfunction "GND65...96_77") (pintype "bidirectional"))
      (node (ref "U1") (pin "78") (pinfunction "GND65...96_78") (pintype "bidirectional"))
      (node (ref "U1") (pin "79") (pinfunction "GND65...96_79") (pintype "bidirectional"))
      (node (ref "U1") (pin "80") (pinfunction "GND65...96_80") (pintype "bidirectional"))
      (node (ref "U1") (pin "81") (pinfunction "GND65...96_81") (pintype "bidirectional"))
      (node (ref "U1") (pin "82") (pinfunction "GND65...96_82") (pintype "bidirectional"))
      (node (ref "U1") (pin "83") (pinfunction "GND65...96_83") (pintype "bidirectional"))
      (node (ref "U1") (pin "84") (pinfunction "GND65...96_84") (pintype "bidirectional"))
      (node (ref "U1") (pin "85") (pinfunction "GND65...96_85") (pintype "bidirectional"))
      (node (ref "U1") (pin "86") (pinfunction "GND65...96_86") (pintype "bidirectional"))
      (node (ref "U1") (pin "87") (pinfunction "GND65...96_87") (pintype "bidirectional"))
      (node (ref "U1") (pin "88") (pinfunction "GND65...96_88") (pintype "bidirectional"))
      (node (ref "U1") (pin "89") (pinfunction "GND65...96_89") (pintype "bidirectional"))
      (node (ref "U1") (pin "9") (pinfunction "DTR_9") (pintype "bidirectional"))
      (node (ref "U1") (pin "90") (pinfunction "GND65...96_90") (pintype "bidirectional"))
      (node (ref "U1") (pin "91") (pinfunction "GND65...96_91") (pintype "bidirectional"))
      (node (ref "U1") (pin "92") (pinfunction "GND65...96_92") (pintype "bidirectional"))
      (node (ref "U1") (pin "93") (pinfunction "GND65...96_93") (pintype "bidirectional"))
      (node (ref "U1") (pin "94") (pinfunction "GND65...96_94") (pintype "bidirectional"))
      (node (ref "U1") (pin "95") (pinfunction "GND65...96_95") (pintype "bidirectional"))
      (node (ref "U1") (pin "96") (pinfunction "GND65...96_96") (pintype "bidirectional"))
      (node (ref "U2") (pin "10") (pinfunction "GND_10") (pintype "bidirectional"))
      (node (ref "U2") (pin "11") (pinfunction "GND_11") (pintype "bidirectional"))
      (node (ref "U3") (pin "12") (pinfunction "VSSA_12") (pintype "power_in"))
      (node (ref "U3") (pin "18") (pinfunction "VSS_4_18") (pintype "power_in"))
      (node (ref "U3") (pin "60") (pinfunction "BOOT0_60") (pintype "bidirectional"))
      (node (ref "U3") (pin "63") (pinfunction "VSS_3_63") (pintype "power_in"))
      (node (ref "U4") (pin "1") (pinfunction "CTG_1") (pintype "bidirectional"))
      (node (ref "U4") (pin "4") (pinfunction "GND_4") (pintype "bidirectional"))
      (node (ref "U4") (pin "6") (pinfunction "QST_6") (pintype "bidirectional"))
      (node (ref "U4") (pin "EP") (pinfunction "GND_EP") (pintype "bidirectional"))
      (node (ref "U5") (pin "3") (pinfunction "GND_3") (pintype "bidirectional"))
      (node (ref "U6") (pin "3") (pinfunction "GND_3") (pintype "bidirectional"))
      (node (ref "U8") (pin "10") (pinfunction "GND_10") (pintype "bidirectional"))
      (node (ref "U8") (pin "11") (pinfunction "GND_11") (pintype "bidirectional"))
      (node (ref "U8") (pin "4") (pinfunction "1DIR_4") (pintype "bidirectional"))
      (node (ref "U8") (pin "5") (pinfunction "2DIR_5") (pintype "bidirectional"))
      (node (ref "X1") (pin "GND") (pinfunction "GND_GND") (pintype "bidirectional"))
      (node (ref "X1") (pin "MT1") (pinfunction "GND_MT1") (pintype "bidirectional"))
      (node (ref "X1") (pin "MT2") (pinfunction "GND_MT2") (pintype "bidirectional"))
    )
    (net (code "37") (name "ILIM") (class "Default")
      (node (ref "R2") (pin "1") (pinfunction "1_1") (pintype "passive"))
      (node (ref "U$1") (pin "10") (pinfunction "ILIM_10") (pintype "output"))
    )
    (net (code "38") (name "LED1") (class "Default")
      (node (ref "BLUE_LED_0603") (pin "A") (pinfunction "A_A") (pintype "passive"))
      (node (ref "R10") (pin "1") (pinfunction "1_1") (pintype "passive"))
    )
    (net (code "39") (name "Net-(LED2-2)") (class "Default")
      (node (ref "LED2") (pin "BLUE") (pinfunction "2_BLUE") (pintype "passive"))
      (node (ref "R11") (pin "1") (pinfunction "1_1") (pintype "passive"))
    )
    (net (code "40") (name "Net-(LED2-3)") (class "Default")
      (node (ref "LED2") (pin "GREEN") (pinfunction "3_GREEN") (pintype "passive"))
      (node (ref "R9") (pin "1") (pinfunction "1_1") (pintype "passive"))
    )
    (net (code "41") (name "Net-(LED2-4)") (class "Default")
      (node (ref "LED2") (pin "RED") (pinfunction "4_RED") (pintype "passive"))
      (node (ref "R12") (pin "1") (pinfunction "1_1") (pintype "passive"))
    )
    (net (code "42") (name "Net-(R4-Pad2)") (class "Default")
      (node (ref "R4") (pin "2") (pinfunction "2_2") (pintype "passive"))
      (node (ref "RED_LED_0603") (pin "C") (pinfunction "C_C") (pintype "passive"))
    )
    (net (code "43") (name "Net-(U$1-INT)") (class "Default")
      (node (ref "R15") (pin "1") (pinfunction "1_1") (pintype "passive"))
      (node (ref "U$1") (pin "7") (pinfunction "INT_7") (pintype "bidirectional"))
    )
    (net (code "44") (name "Net-(U$1-OTG)") (class "Default")
      (node (ref "R16") (pin "1") (pinfunction "1_1") (pintype "passive"))
      (node (ref "U$1") (pin "8") (pinfunction "OTG_8") (pintype "bidirectional"))
    )
    (net (code "45") (name "Net-(U$1-TS)") (class "Default")
      (node (ref "R18") (pin "2") (pinfunction "2_2") (pintype "passive"))
      (node (ref "R19") (pin "1") (pinfunction "1_1") (pintype "passive"))
      (node (ref "R20") (pin "1") (pinfunction "1_1") (pintype "passive"))
      (node (ref "U$1") (pin "11") (pinfunction "TS_11") (pintype "bidirectional"))
    )
    (net (code "46") (name "Net-(U$1-~{PG})") (class "Default")
      (node (ref "R7") (pin "1") (pinfunction "1_1") (pintype "passive"))
      (node (ref "U$1") (pin "3") (pinfunction "~{PG}_3") (pintype "output"))
    )
    (net (code "47") (name "Net-(U$1-~{QON})") (class "Default")
      (node (ref "R20") (pin "2") (pinfunction "2_2") (pintype "passive"))
      (node (ref "U$1") (pin "12") (pinfunction "~{QON}_12") (pintype "bidirectional"))
    )
    (net (code "48") (name "Net-(U$5-PadB2)") (class "Default")
      (node (ref "U$5") (pin "B2") (pinfunction "B2_B2") (pintype "bidirectional"))
      (node (ref "U$6") (pin "1") (pinfunction "1_1") (pintype "passive"))
    )
    (net (code "49") (name "Net-(U3-VCAP_1)") (class "Default")
      (node (ref "C35") (pin "1") (pinfunction "1_1") (pintype "passive"))
      (node (ref "U3") (pin "31") (pinfunction "VCAP_1_31") (pintype "power_in"))
    )
    (net (code "50") (name "Net-(U3-VCAP_2)") (class "Default")
      (node (ref "C32") (pin "1") (pinfunction "1_1") (pintype "passive"))
      (node (ref "U3") (pin "47") (pinfunction "VCAP_2_47") (pintype "power_in"))
    )
    (net (code "51") (name "Net-(U4-CELL)") (class "Default")
      (node (ref "C39") (pin "1") (pinfunction "1_1") (pintype "passive"))
      (node (ref "R23") (pin "1") (pinfunction "1_1") (pintype "passive"))
      (node (ref "U4") (pin "2") (pinfunction "CELL_2") (pintype "bidirectional"))
    )
    (net (code "52") (name "Net-(U4-VDD)") (class "Default")
      (node (ref "C38") (pin "1") (pinfunction "1_1") (pintype "passive"))
      (node (ref "R22") (pin "1") (pinfunction "1_1") (pintype "passive"))
      (node (ref "U4") (pin "3") (pinfunction "VDD_3") (pintype "bidirectional"))
    )
    (net (code "53") (name "OSC32_IN_UC") (class "Default")
      (node (ref "C34") (pin "1") (pinfunction "1_1") (pintype "passive"))
      (node (ref "U3") (pin "3") (pinfunction "PC14_3") (pintype "bidirectional"))
      (node (ref "Y1") (pin "X1") (pinfunction "1_X1") (pintype "passive"))
    )
    (net (code "54") (name "OSC32_OUT_UC") (class "Default")
      (node (ref "C33") (pin "1") (pinfunction "1_1") (pintype "passive"))
      (node (ref "U3") (pin "4") (pinfunction "PC15_4") (pintype "bidirectional"))
      (node (ref "Y1") (pin "X2") (pinfunction "2_X2") (pintype "passive"))
    )
    (net (code "55") (name "OSC_IN_UC") (class "Default")
      (node (ref "C28") (pin "1") (pinfunction "1_1") (pintype "passive"))
      (node (ref "U3") (pin "5") (pinfunction "PH0/OSC_IN_5") (pintype "bidirectional"))
      (node (ref "Y2") (pin "1") (pinfunction "1_1") (pintype "passive"))
    )
    (net (code "56") (name "OSC_OUT_UC") (class "Default")
      (node (ref "C26") (pin "1") (pinfunction "1_1") (pintype "passive"))
      (node (ref "U3") (pin "6") (pinfunction "PH1/OSC_OUT_6") (pintype "bidirectional"))
      (node (ref "Y2") (pin "3") (pinfunction "2_3") (pintype "passive"))
    )
    (net (code "57") (name "PA8_PM_SCL") (class "Default")
      (node (ref "R14") (pin "1") (pinfunction "1_1") (pintype "passive"))
      (node (ref "U$1") (pin "5") (pinfunction "SCL_5") (pintype "output"))
      (node (ref "U3") (pin "41") (pinfunction "PA8_41") (pintype "bidirectional"))
      (node (ref "U4") (pin "7") (pinfunction "SCL_7") (pintype "bidirectional"))
    )
    (net (code "58") (name "PC9_PM_SDA") (class "Default")
      (node (ref "R13") (pin "1") (pinfunction "1_1") (pintype "passive"))
      (node (ref "U$1") (pin "6") (pinfunction "SDA_6") (pintype "bidirectional"))
      (node (ref "U3") (pin "40") (pinfunction "PC9_40") (pintype "bidirectional"))
      (node (ref "U4") (pin "8") (pinfunction "SDA_8") (pintype "bidirectional"))
    )
    (net (code "59") (name "PMID") (class "Default")
      (node (ref "C5") (pin "1") (pinfunction "1_1") (pintype "passive"))
      (node (ref "U$1") (pin "23") (pinfunction "PMID_23") (pintype "passive"))
    )
    (net (code "60") (name "PWR_UB") (class "Default")
      (node (ref "R1") (pin "1") (pinfunction "1_1") (pintype "passive"))
      (node (ref "U1") (pin "15") (pinfunction "PWR_ON_15") (pintype "bidirectional"))
      (node (ref "U5") (pin "4") (pinfunction "B_4") (pintype "bidirectional"))
    )
    (net (code "61") (name "PWR_UC") (class "Default")
      (node (ref "U3") (pin "28") (pinfunction "PB2_28") (pintype "bidirectional"))
      (node (ref "U5") (pin "2") (pinfunction "A_2") (pintype "bidirectional"))
    )
    (net (code "62") (name "REGN") (class "Default")
      (node (ref "C25") (pin "1") (pinfunction "1_1") (pintype "passive"))
      (node (ref "R18") (pin "1") (pinfunction "1_1") (pintype "passive"))
      (node (ref "U$1") (pin "22") (pinfunction "REGN_22") (pintype "bidirectional"))
    )
    (net (code "63") (name "RESET_UB") (class "Default")
      (node (ref "U1") (pin "18") (pinfunction "RESET_N_18") (pintype "bidirectional"))
      (node (ref "U6") (pin "4") (pinfunction "B_4") (pintype "bidirectional"))
    )
    (net (code "64") (name "RESET_UC") (class "Default")
      (node (ref "U3") (pin "24") (pinfunction "PC4_24") (pintype "bidirectional"))
      (node (ref "U6") (pin "2") (pinfunction "A_2") (pintype "bidirectional"))
    )
    (net (code "65") (name "RGB_BLUE") (class "Default")
      (node (ref "R11") (pin "2") (pinfunction "2_2") (pintype "passive"))
      (node (ref "U3") (pin "17") (pinfunction "PA3_17") (pintype "bidirectional"))
    )
    (net (code "66") (name "RGB_GREEN") (class "Default")
      (node (ref "R9") (pin "2") (pinfunction "2_2") (pintype "passive"))
      (node (ref "U3") (pin "16") (pinfunction "PA2_16") (pintype "bidirectional"))
    )
    (net (code "67") (name "RGB_RED") (class "Default")
      (node (ref "R12") (pin "2") (pinfunction "2_2") (pintype "passive"))
      (node (ref "U3") (pin "15") (pinfunction "PA1_15") (pintype "bidirectional"))
    )
    (net (code "68") (name "RI_UB") (class "Default")
      (node (ref "U1") (pin "7") (pinfunction "RI_7") (pintype "bidirectional"))
      (node (ref "U8") (pin "14") (pinfunction "1B2_14") (pintype "bidirectional"))
    )
    (net (code "69") (name "RI_UC") (class "Default")
      (node (ref "U3") (pin "33") (pinfunction "PB12_33") (pintype "bidirectional"))
      (node (ref "U8") (pin "7") (pinfunction "1A2_7") (pintype "bidirectional"))
    )
    (net (code "70") (name "RTS_UB") (class "Default")
      (node (ref "U1") (pin "10") (pinfunction "RTS_10") (pintype "bidirectional"))
      (node (ref "U2") (pin "15") (pinfunction "1B1_15") (pintype "bidirectional"))
    )
    (net (code "71") (name "RTS_UC") (class "Default")
      (node (ref "U2") (pin "6") (pinfunction "1A1_6") (pintype "bidirectional"))
      (node (ref "U3") (pin "35") (pinfunction "PB14_35") (pintype "bidirectional"))
    )
    (net (code "72") (name "RX") (class "Default")
      (node (ref "JP1") (pin "4") (pinfunction "4_4") (pintype "passive"))
      (node (ref "U3") (pin "43") (pinfunction "PA10_43") (pintype "bidirectional"))
    )
    (net (code "73") (name "RXD_UB") (class "Default")
      (node (ref "U1") (pin "13") (pinfunction "RXD_13") (pintype "bidirectional"))
      (node (ref "U8") (pin "13") (pinfunction "2B1_13") (pintype "bidirectional"))
    )
    (net (code "74") (name "RXD_UC") (class "Default")
      (node (ref "U3") (pin "30") (pinfunction "PB11_30") (pintype "bidirectional"))
      (node (ref "U8") (pin "8") (pinfunction "2A1_8") (pintype "bidirectional"))
    )
    (net (code "75") (name "SIM_CLK") (class "Default")
      (node (ref "C12") (pin "1") (pinfunction "1_1") (pintype "passive"))
      (node (ref "J1") (pin "C3") (pinfunction "CLK_C3") (pintype "passive"))
      (node (ref "U1") (pin "38") (pinfunction "SIM_CLK_38") (pintype "bidirectional"))
    )
    (net (code "76") (name "SIM_DET") (class "Default")
      (node (ref "U1") (pin "42") (pinfunction "SIM_DET_42") (pintype "bidirectional"))
    )
    (net (code "77") (name "SIM_IO") (class "Default")
      (node (ref "C13") (pin "1") (pinfunction "1_1") (pintype "passive"))
      (node (ref "J1") (pin "C7") (pinfunction "I/O_C7") (pintype "passive"))
      (node (ref "U1") (pin "39") (pinfunction "SIM_IO_39") (pintype "bidirectional"))
    )
    (net (code "78") (name "SIM_RST") (class "Default")
      (node (ref "C10") (pin "1") (pinfunction "1_1") (pintype "passive"))
      (node (ref "J1") (pin "C2") (pinfunction "RST_C2") (pintype "passive"))
      (node (ref "U1") (pin "40") (pinfunction "SIM_RST_40") (pintype "bidirectional"))
    )
    (net (code "79") (name "SIM_VCC") (class "Default")
      (node (ref "C11") (pin "1") (pinfunction "1_1") (pintype "passive"))
      (node (ref "C14") (pin "1") (pinfunction "1_1") (pintype "passive"))
      (node (ref "J1") (pin "C1") (pinfunction "VCC_C1") (pintype "passive"))
      (node (ref "J1") (pin "C6") (pinfunction "VPP_C6") (pintype "passive"))
      (node (ref "U1") (pin "41") (pinfunction "VSIM_41") (pintype "bidirectional"))
    )
    (net (code "80") (name "STAT") (class "Default")
      (node (ref "R4") (pin "1") (pinfunction "1_1") (pintype "passive"))
      (node (ref "U$1") (pin "4") (pinfunction "STAT_4") (pintype "bidirectional"))
    )
    (net (code "81") (name "SW") (class "Default")
      (node (ref "C7") (pin "2") (pinfunction "2_2") (pintype "passive"))
      (node (ref "U$1") (pin "19") (pinfunction "SW_19") (pintype "power_in"))
      (node (ref "U$1") (pin "20") (pinfunction "SW_20") (pintype "power_in"))
      (node (ref "U$4") (pin "P$1") (pinfunction "1_P$1") (pintype "bidirectional"))
    )
    (net (code "82") (name "TX") (class "Default")
      (node (ref "JP1") (pin "3") (pinfunction "3_3") (pintype "passive"))
      (node (ref "U3") (pin "42") (pinfunction "PA9_42") (pintype "bidirectional"))
    )
    (net (code "83") (name "TXD_UB") (class "Default")
      (node (ref "U1") (pin "12") (pinfunction "TXD_12") (pintype "bidirectional"))
      (node (ref "U2") (pin "14") (pinfunction "1B2_14") (pintype "bidirectional"))
    )
    (net (code "84") (name "TXD_UC") (class "Default")
      (node (ref "U2") (pin "7") (pinfunction "1A2_7") (pintype "bidirectional"))
      (node (ref "U3") (pin "29") (pinfunction "PB10_29") (pintype "bidirectional"))
    )
    (net (code "85") (name "USB_DM") (class "Default")
      (node (ref "R6") (pin "2") (pinfunction "2_2") (pintype "passive"))
      (node (ref "R7") (pin "2") (pinfunction "2_2") (pintype "passive"))
      (node (ref "U$7") (pin "P$2") (pinfunction "P$2_P$2") (pintype "bidirectional"))
      (node (ref "X1") (pin "D-") (pinfunction "D-_D-") (pintype "bidirectional"))
    )
    (net (code "86") (name "USB_DM_UC") (class "Default")
      (node (ref "R6") (pin "1") (pinfunction "1_1") (pintype "passive"))
      (node (ref "U3") (pin "44") (pinfunction "PA11_44") (pintype "bidirectional"))
    )
    (net (code "87") (name "USB_DP") (class "Default")
      (node (ref "R5") (pin "2") (pinfunction "2_2") (pintype "passive"))
      (node (ref "U$1") (pin "2") (pinfunction "PSEL_2") (pintype "output"))
      (node (ref "U$7") (pin "P$1") (pinfunction "P$1_P$1") (pintype "bidirectional"))
      (node (ref "X1") (pin "D+") (pinfunction "D+_D+") (pintype "bidirectional"))
    )
    (net (code "88") (name "USB_DP_UC") (class "Default")
      (node (ref "R5") (pin "1") (pinfunction "1_1") (pintype "passive"))
      (node (ref "U3") (pin "45") (pinfunction "PA12_45") (pintype "bidirectional"))
    )
    (net (code "89") (name "VBAT") (class "Default")
      (node (ref "JP2") (pin "3") (pinfunction "3_3") (pintype "passive"))
      (node (ref "U3") (pin "1") (pinfunction "VBAT_1") (pintype "power_in"))
    )
    (net (code "90") (name "VBUS") (class "Default")
      (node (ref "U$3") (pin "ANODE") (pinfunction "ANODE_ANODE") (pintype "bidirectional"))
      (node (ref "X1") (pin "VBUS") (pinfunction "VBUS_VBUS") (pintype "bidirectional"))
    )
    (net (code "91") (name "VIN") (class "Default")
      (node (ref "C4") (pin "1") (pinfunction "1_1") (pintype "passive"))
      (node (ref "JP1") (pin "1") (pinfunction "1_1") (pintype "passive"))
      (node (ref "U$1") (pin "1") (pinfunction "VBUS_1") (pintype "power_in"))
      (node (ref "U$1") (pin "24") (pinfunction "VBUS_24") (pintype "passive"))
      (node (ref "U$3") (pin "CATHODE") (pinfunction "CATHODE_CATHODE") (pintype "bidirectional"))
    )
    (net (code "92") (name "V_BCKP") (class "Default")
      (node (ref "R1") (pin "2") (pinfunction "2_2") (pintype "passive"))
      (node (ref "U1") (pin "2") (pinfunction "V_BCKP_2") (pintype "bidirectional"))
    )
    (net (code "93") (name "V_INT") (class "Default")
      (node (ref "C21") (pin "1") (pinfunction "1_1") (pintype "passive"))
      (node (ref "C22") (pin "1") (pinfunction "1_1") (pintype "passive"))
      (node (ref "U1") (pin "4") (pinfunction "V_INT_4") (pintype "bidirectional"))
      (node (ref "U2") (pin "2") (pinfunction "VCCB_2") (pintype "bidirectional"))
      (node (ref "U8") (pin "2") (pinfunction "VCCB_2") (pintype "bidirectional"))
    )
    (net (code "94") (name "WKP") (class "Default")
      (node (ref "JP1") (pin "5") (pinfunction "5_5") (pintype "passive"))
      (node (ref "U3") (pin "14") (pinfunction "WKUP/PA0_14") (pintype "bidirectional"))
    )
    (net (code "95") (name "unconnected-(MODE-Pad4)") (class "Default")
      (node (ref "MODE") (pin "4") (pinfunction "4_4") (pintype "passive"))
    )
    (net (code "96") (name "unconnected-(RESET-Pad1)") (class "Default")
      (node (ref "RESET") (pin "1") (pinfunction "1_1") (pintype "passive"))
    )
    (net (code "97") (name "unconnected-(U1-DCD-Pad8)") (class "Default")
      (node (ref "U1") (pin "8") (pinfunction "DCD_8") (pintype "bidirectional"))
    )
    (net (code "98") (name "unconnected-(U1-DSR-Pad6)") (class "Default")
      (node (ref "U1") (pin "6") (pinfunction "DSR_6") (pintype "bidirectional"))
    )
    (net (code "99") (name "unconnected-(U1-GPIO1-Pad16)") (class "Default")
      (node (ref "U1") (pin "16") (pinfunction "GPIO1_16") (pintype "bidirectional"))
    )
    (net (code "100") (name "unconnected-(U1-GPIO2-Pad23)") (class "Default")
      (node (ref "U1") (pin "23") (pinfunction "GPIO2_23") (pintype "bidirectional"))
    )
    (net (code "101") (name "unconnected-(U1-GPIO3-Pad24)") (class "Default")
      (node (ref "U1") (pin "24") (pinfunction "GPIO3_24") (pintype "bidirectional"))
    )
    (net (code "102") (name "unconnected-(U1-GPIO4-Pad25)") (class "Default")
      (node (ref "U1") (pin "25") (pinfunction "GPIO4_25") (pintype "bidirectional"))
    )
    (net (code "103") (name "unconnected-(U1-I2S_CLK-Pad36)") (class "Default")
      (node (ref "U1") (pin "36") (pinfunction "I2S_CLK_36") (pintype "bidirectional"))
    )
    (net (code "104") (name "unconnected-(U1-I2S_RXD-Pad37)") (class "Default")
      (node (ref "U1") (pin "37") (pinfunction "I2S_RXD_37") (pintype "bidirectional"))
    )
    (net (code "105") (name "unconnected-(U1-I2S_TXD-Pad35)") (class "Default")
      (node (ref "U1") (pin "35") (pinfunction "I2S_TXD_35") (pintype "bidirectional"))
    )
    (net (code "106") (name "unconnected-(U1-I2S_WA-Pad34)") (class "Default")
      (node (ref "U1") (pin "34") (pinfunction "I2S_WA_34") (pintype "bidirectional"))
    )
    (net (code "107") (name "unconnected-(U1-MIC_BIAS-Pad46)") (class "Default")
      (node (ref "U1") (pin "46") (pinfunction "MIC_BIAS_46") (pintype "bidirectional"))
    )
    (net (code "108") (name "unconnected-(U1-MIC_GND-Pad47)") (class "Default")
      (node (ref "U1") (pin "47") (pinfunction "MIC_GND_47") (pintype "bidirectional"))
    )
    (net (code "109") (name "unconnected-(U1-MIC_N-Pad48)") (class "Default")
      (node (ref "U1") (pin "48") (pinfunction "MIC_N_48") (pintype "bidirectional"))
    )
    (net (code "110") (name "unconnected-(U1-MIC_P-Pad49)") (class "Default")
      (node (ref "U1") (pin "49") (pinfunction "MIC_P_49") (pintype "bidirectional"))
    )
    (net (code "111") (name "unconnected-(U1-RSVD-Pad19)") (class "Default")
      (node (ref "U1") (pin "19") (pinfunction "RSVD_19") (pintype "bidirectional"))
    )
    (net (code "112") (name "unconnected-(U1-RSVD-Pad31)") (class "Default")
      (node (ref "U1") (pin "31") (pinfunction "RSVD_31") (pintype "bidirectional"))
    )
    (net (code "113") (name "unconnected-(U1-RXD_AUX{slash}USB_D--Pad28)") (class "Default")
      (node (ref "U1") (pin "28") (pinfunction "RXD_AUX/USB_D-_28") (pintype "bidirectional"))
    )
    (net (code "114") (name "unconnected-(U1-SCL-Pad27)") (class "Default")
      (node (ref "U1") (pin "27") (pinfunction "SCL_27") (pintype "bidirectional"))
    )
    (net (code "115") (name "unconnected-(U1-SDA-Pad26)") (class "Default")
      (node (ref "U1") (pin "26") (pinfunction "SDA_26") (pintype "bidirectional"))
    )
    (net (code "116") (name "unconnected-(U1-SPK_N-Pad45)") (class "Default")
      (node (ref "U1") (pin "45") (pinfunction "SPK_N_45") (pintype "bidirectional"))
    )
    (net (code "117") (name "unconnected-(U1-SPK_P-Pad44)") (class "Default")
      (node (ref "U1") (pin "44") (pinfunction "SPK_P_44") (pintype "bidirectional"))
    )
    (net (code "118") (name "unconnected-(U1-TXD_AUX{slash}USB_D+-Pad29)") (class "Default")
      (node (ref "U1") (pin "29") (pinfunction "TXD_AUX/USB_D+_29") (pintype "bidirectional"))
    )
    (net (code "119") (name "unconnected-(U1-VUSB_DET-Pad17)") (class "Default")
      (node (ref "U1") (pin "17") (pinfunction "VUSB_DET_17") (pintype "bidirectional"))
    )
    (net (code "120") (name "unconnected-(U2-2A1-Pad8)") (class "Default")
      (node (ref "U2") (pin "8") (pinfunction "2A1_8") (pintype "bidirectional"))
    )
    (net (code "121") (name "unconnected-(U2-2A2-Pad9)") (class "Default")
      (node (ref "U2") (pin "9") (pinfunction "2A2_9") (pintype "bidirectional"))
    )
    (net (code "122") (name "unconnected-(U2-2B1-Pad13)") (class "Default")
      (node (ref "U2") (pin "13") (pinfunction "2B1_13") (pintype "bidirectional"))
    )
    (net (code "123") (name "unconnected-(U2-2B2-Pad12)") (class "Default")
      (node (ref "U2") (pin "12") (pinfunction "2B2_12") (pintype "bidirectional"))
    )
    (net (code "124") (name "unconnected-(U8-2A2-Pad9)") (class "Default")
      (node (ref "U8") (pin "9") (pinfunction "2A2_9") (pintype "bidirectional"))
    )
    (net (code "125") (name "unconnected-(U8-2B2-Pad12)") (class "Default")
      (node (ref "U8") (pin "12") (pinfunction "2B2_12") (pintype "bidirectional"))
    )
    (net (code "126") (name "~{CE}") (class "Default")
      (node (ref "R17") (pin "1") (pinfunction "1_1") (pintype "passive"))
      (node (ref "U$1") (pin "9") (pinfunction "~{CE}_9") (pintype "output"))
    )
    (net (code "127") (name "~{LOW_BAT_INT_UC}") (class "Default")
      (node (ref "R21") (pin "1") (pinfunction "1_1") (pintype "passive"))
      (node (ref "U3") (pin "2") (pinfunction "PC13_2") (pintype "bidirectional"))
      (node (ref "U4") (pin "5") (pinfunction "ALT_5") (pintype "bidirectional"))
    )
    (net (code "128") (name "~{LVLOE_UC}") (class "Default")
      (node (ref "R3") (pin "1") (pinfunction "1_1") (pintype "passive"))
      (node (ref "U2") (pin "1") (pinfunction "1/OE_1") (pintype "bidirectional"))
      (node (ref "U2") (pin "16") (pinfunction "2/OE_16") (pintype "bidirectional"))
      (node (ref "U3") (pin "36") (pinfunction "PB15_36") (pintype "bidirectional"))
      (node (ref "U8") (pin "1") (pinfunction "1/OE_1") (pintype "bidirectional"))
      (node (ref "U8") (pin "16") (pinfunction "2/OE_16") (pintype "bidirectional"))
    )
    (net (code "129") (name "~{MODE}") (class "Default")
      (node (ref "MODE") (pin "3") (pinfunction "3_3") (pintype "passive"))
      (node (ref "U3") (pin "38") (pinfunction "PC7_38") (pintype "bidirectional"))
    )
    (net (code "130") (name "~{RST}") (class "Default")
      (node (ref "C6") (pin "1") (pinfunction "1_1") (pintype "passive"))
      (node (ref "JP2") (pin "2") (pinfunction "2_2") (pintype "passive"))
      (node (ref "R8") (pin "1") (pinfunction "1_1") (pintype "passive"))
      (node (ref "RESET") (pin "2") (pinfunction "2_2") (pintype "passive"))
      (node (ref "U3") (pin "7") (pinfunction "NRST_7") (pintype "power_in"))
    )
  )
)
